# SenLEDFet.net
KiCad netlist of a schematic drawn in Altium Designer
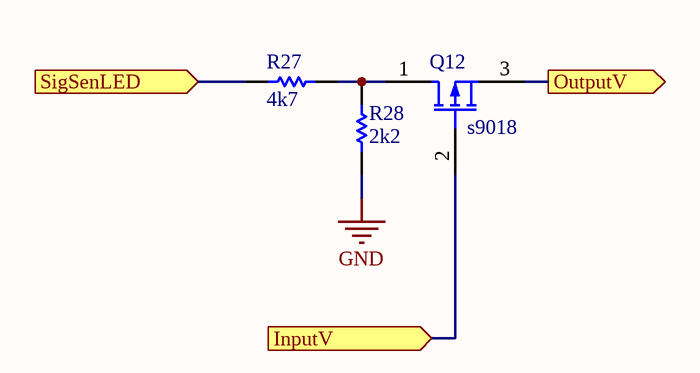
[diagram p0: SenLEDFet.SchDoc]

(export (version "E")
  (design (tool "Eeschema 10.0.6"))
  (components
    (comp (ref "Q12")
      (value "s9018")
      (footprint "SOT-23_N")
      (description "P-Channel MOSFET")
      (fields (field (name "PUBLISHER") "Altium Limited"))
      (libsource (lib "Miscellaneous Devices") (part "MOSFET-P"))
    )
    (comp (ref "R27")
      (value "4k7")
      (footprint "6-0805_L")
      (description "Resistor")
      (fields (field (name "Comment") "R4k7") (field (name "PUBLISHER") "Altium Limited"))
      (libsource (lib "Miscellaneous Devices") (part "Res1"))
    )
    (comp (ref "R28")
      (value "2k2")
      (footprint "6-0805_L")
      (description "Resistor")
      (fields (field (name "Comment") "R2k2") (field (name "PUBLISHER") "Altium Limited"))
      (libsource (lib "Miscellaneous Devices") (part "Res1"))
    )
  )
  (nets
    (net (code "2") (name "/InputV") (class "Default")
      (node (ref "Q12") (pin "2") (pinfunction "G_2") (pintype "passive"))
    )
    (net (code "3") (name "/OutputV") (class "Default")
      (node (ref "Q12") (pin "3") (pinfunction "S_3") (pintype "passive"))
    )
    (net (code "4") (name "/SigSenLED") (class "Default")
      (node (ref "R27") (pin "2") (pinfunction "2_2") (pintype "passive"))
    )
    (net (code "5") (name "GND") (class "Default")
      (node (ref "R28") (pin "2") (pinfunction "2_2") (pintype "passive"))
    )
    (net (code "6") (name "Net-(Q12-D)") (class "Default")
      (node (ref "Q12") (pin "1") (pinfunction "D_1") (pintype "passive"))
      (node (ref "R27") (pin "1") (pinfunction "1_1") (pintype "passive"))
      (node (ref "R28") (pin "1") (pinfunction "1_1") (pintype "passive"))
    )
  )
)
